# revB.net
KiCad netlist of a schematic drawn in EAGLE
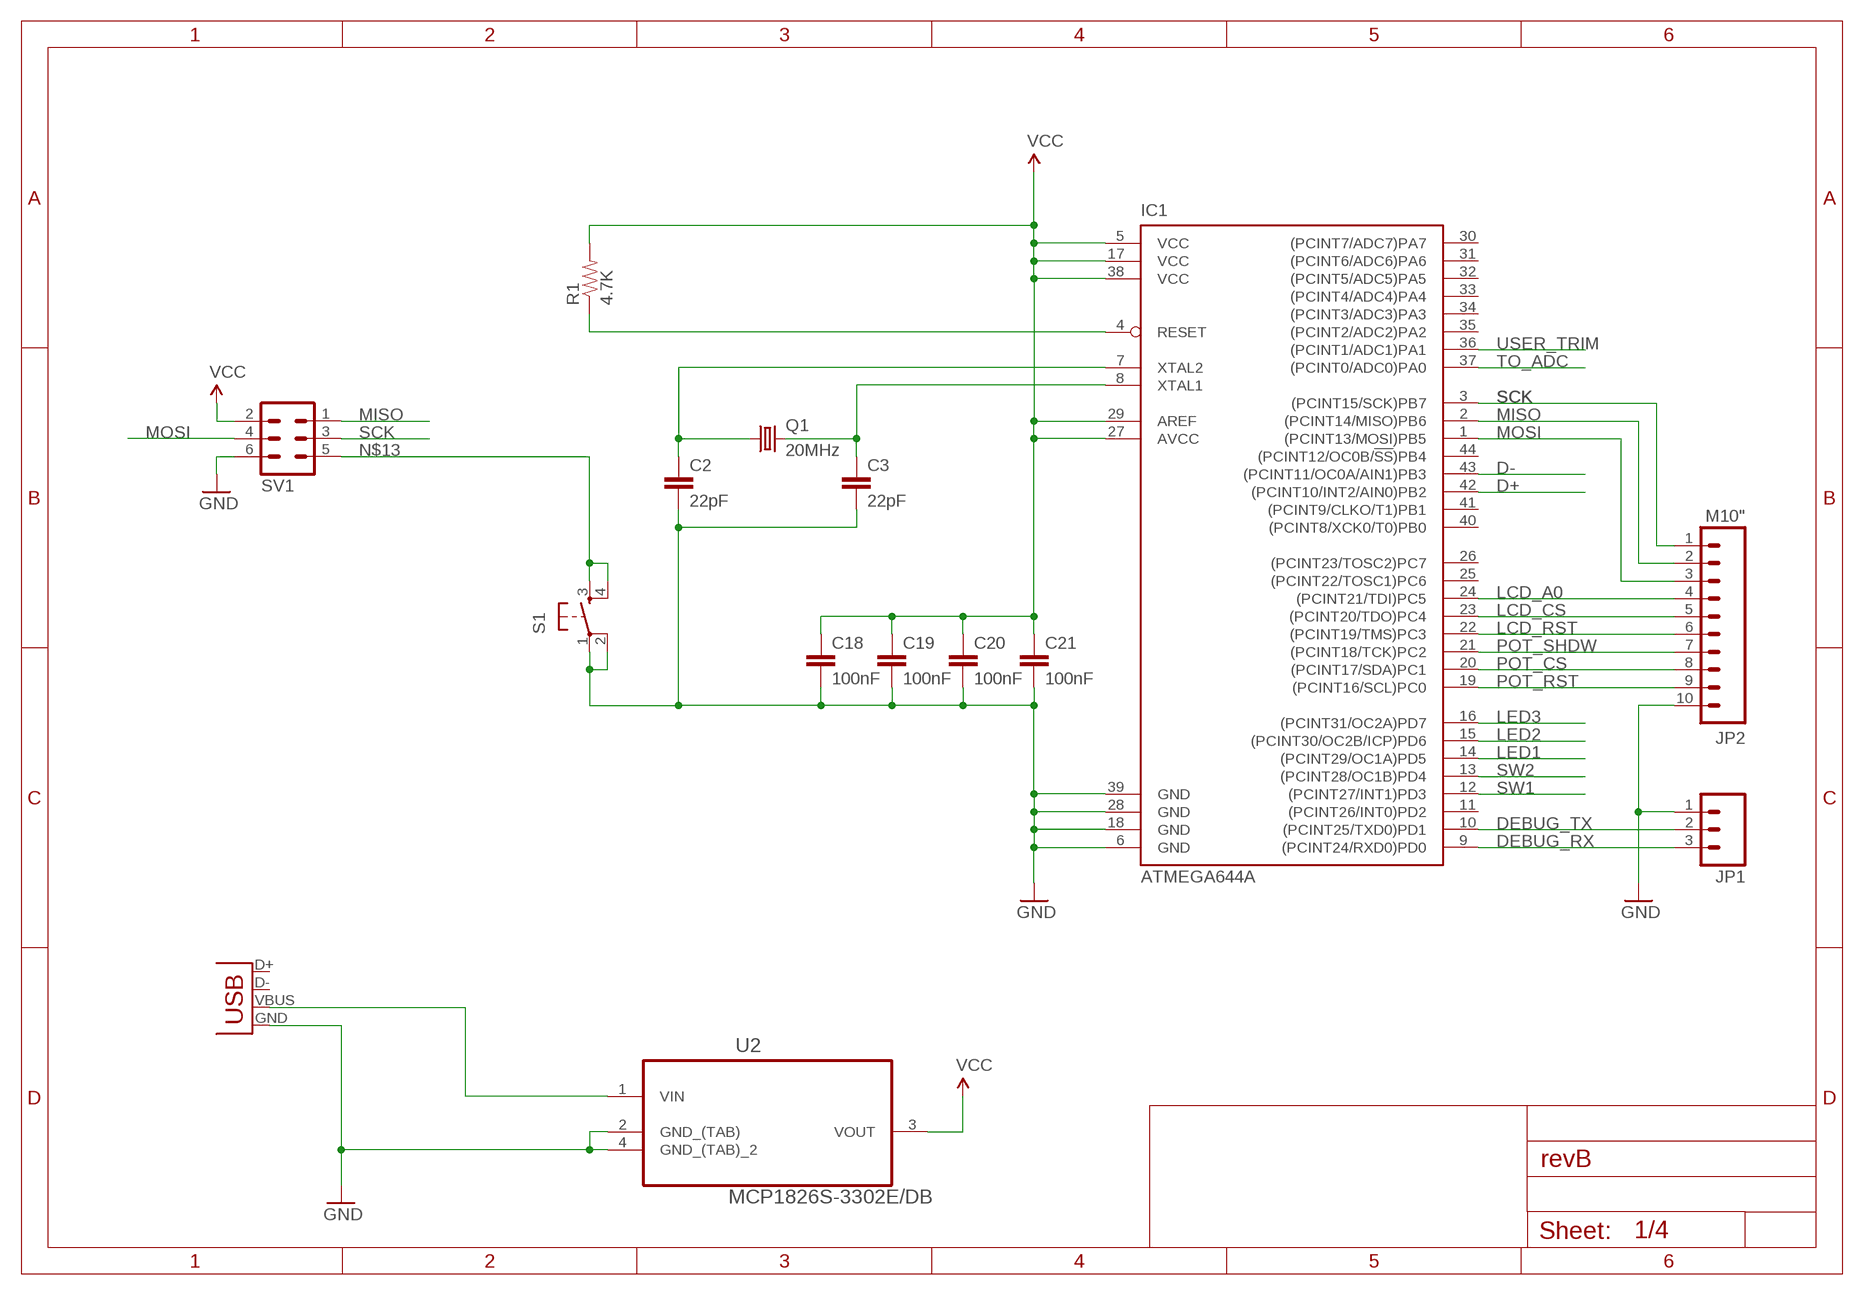
[diagram p0: schematic, sheet 1]
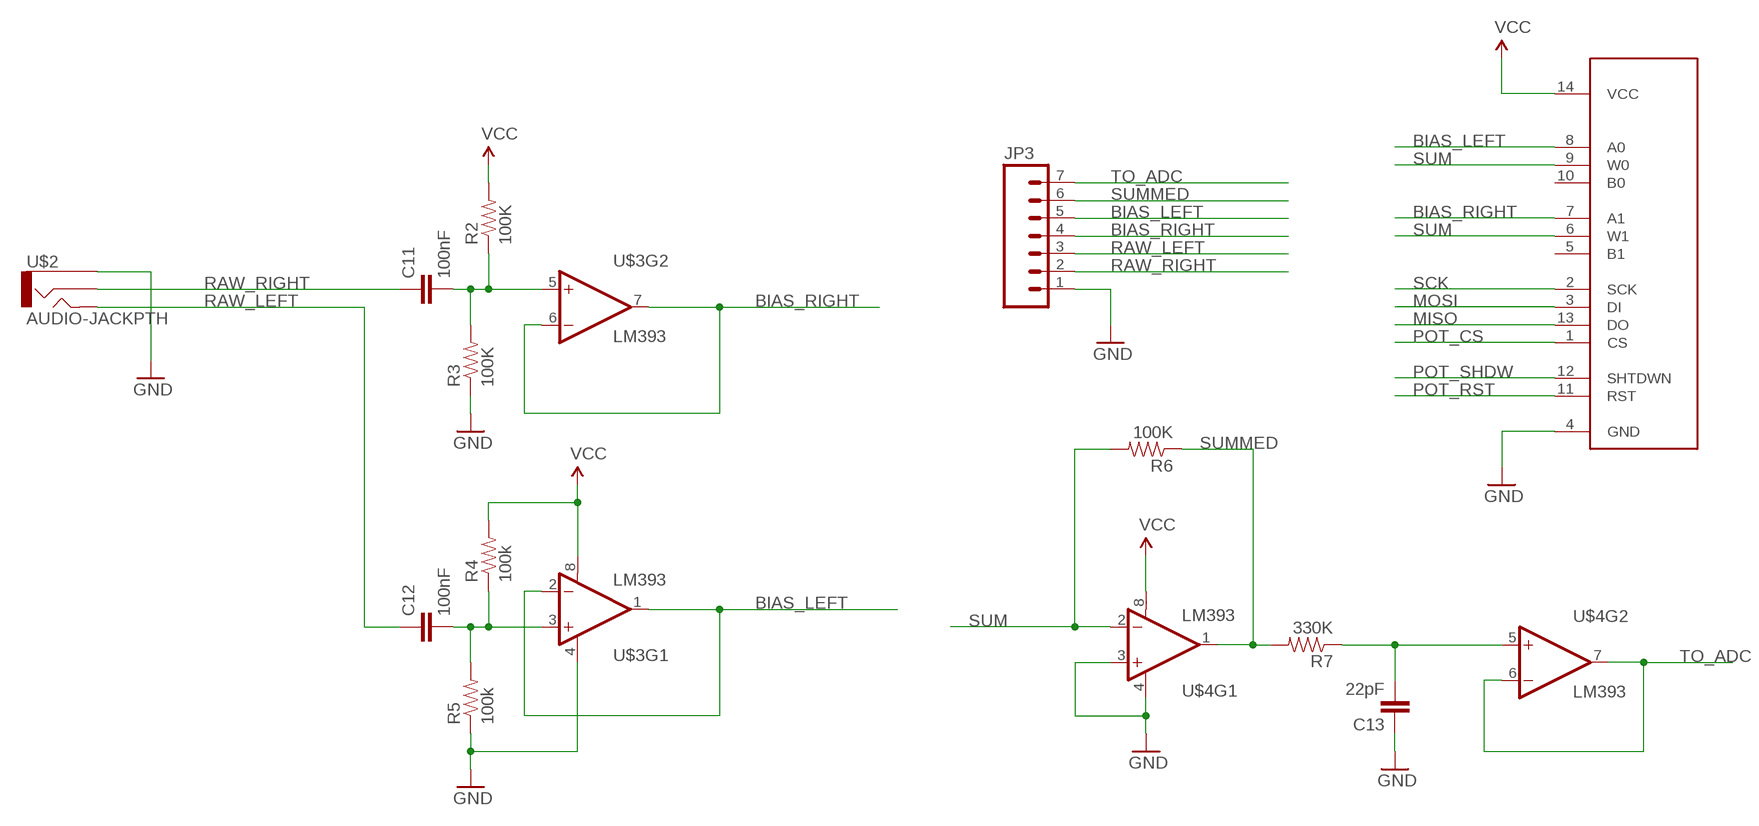
[diagram p1: schematic, sheet 2]
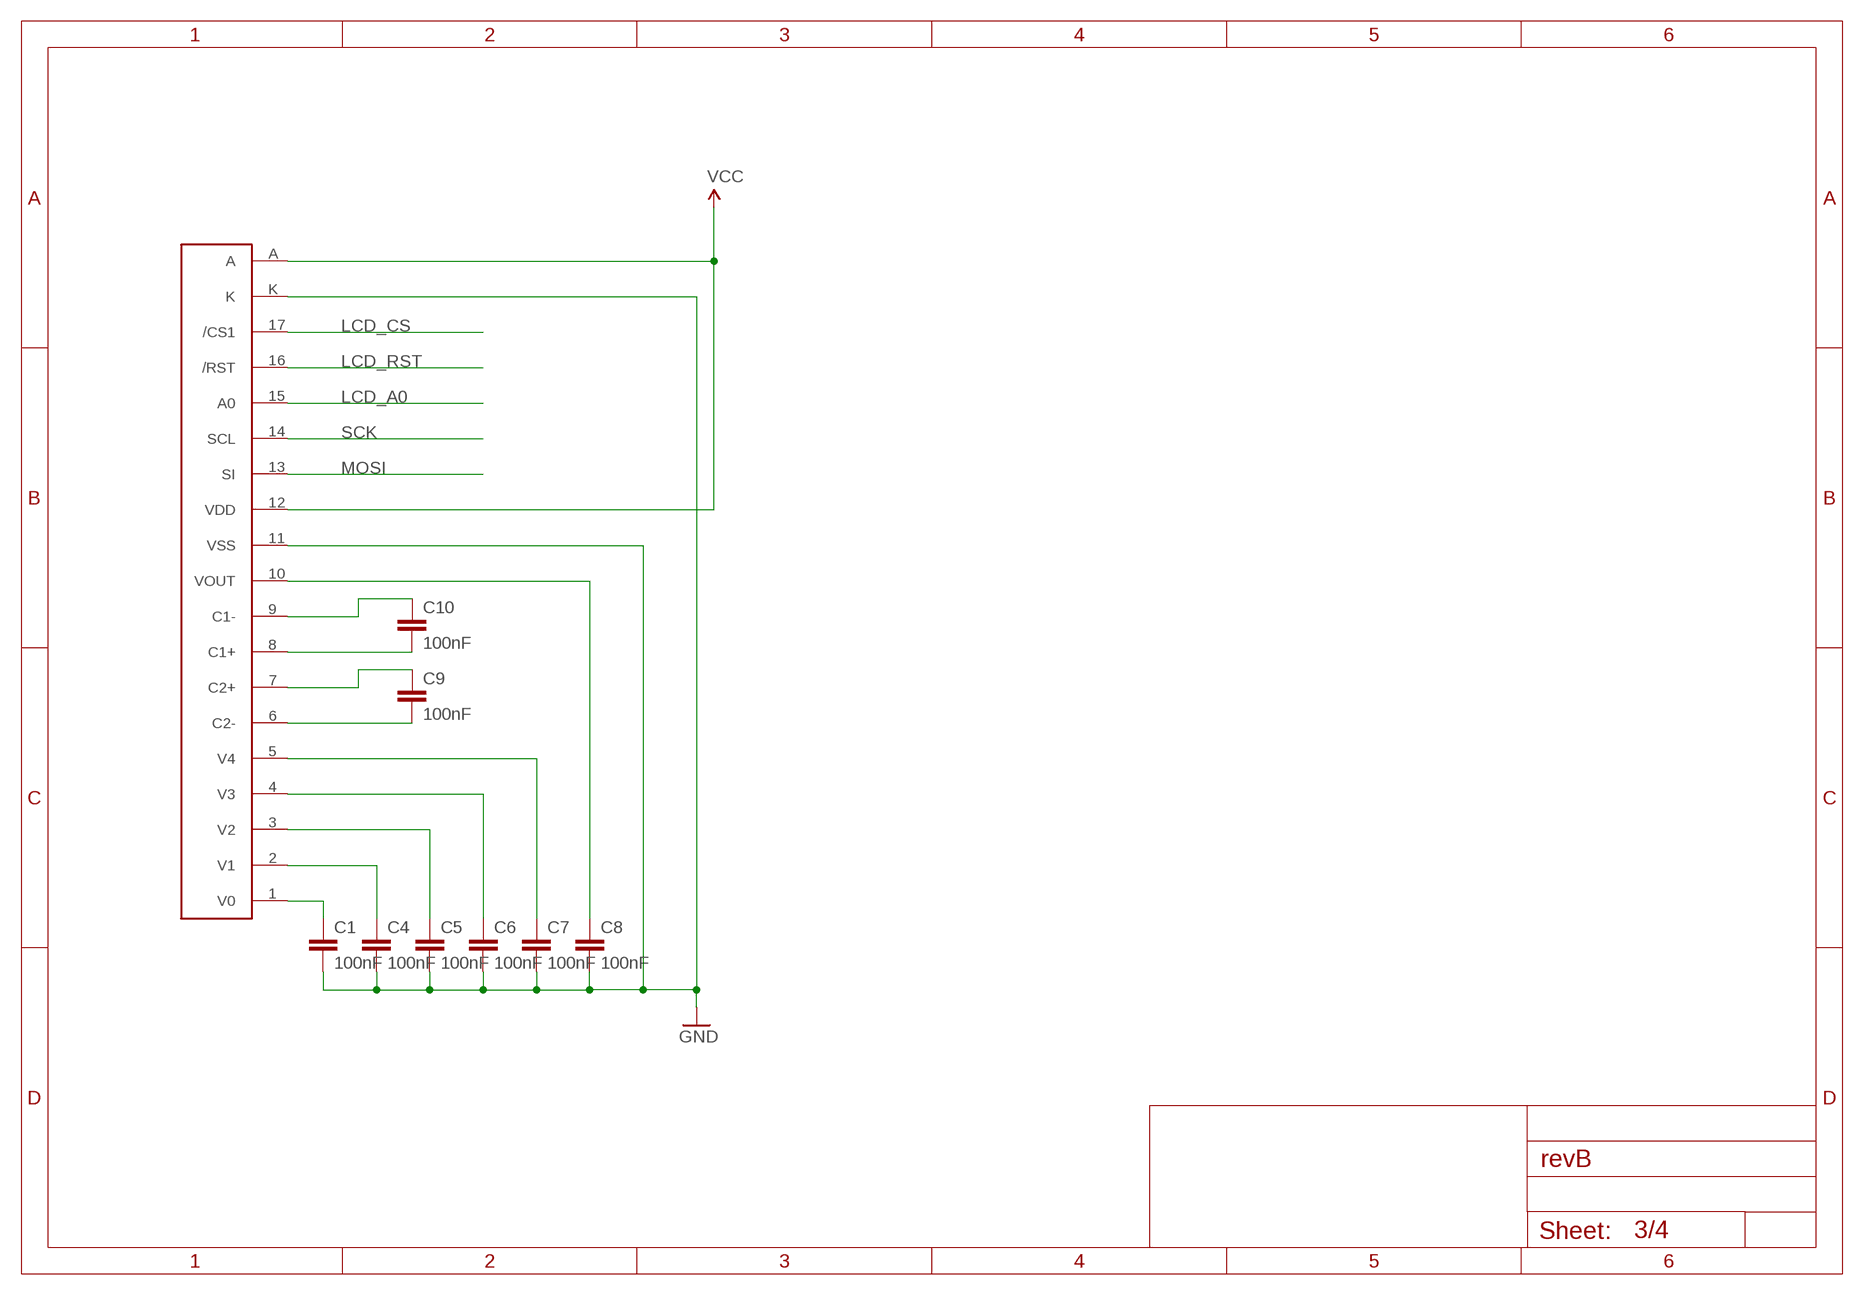
[diagram p2: schematic, sheet 3]
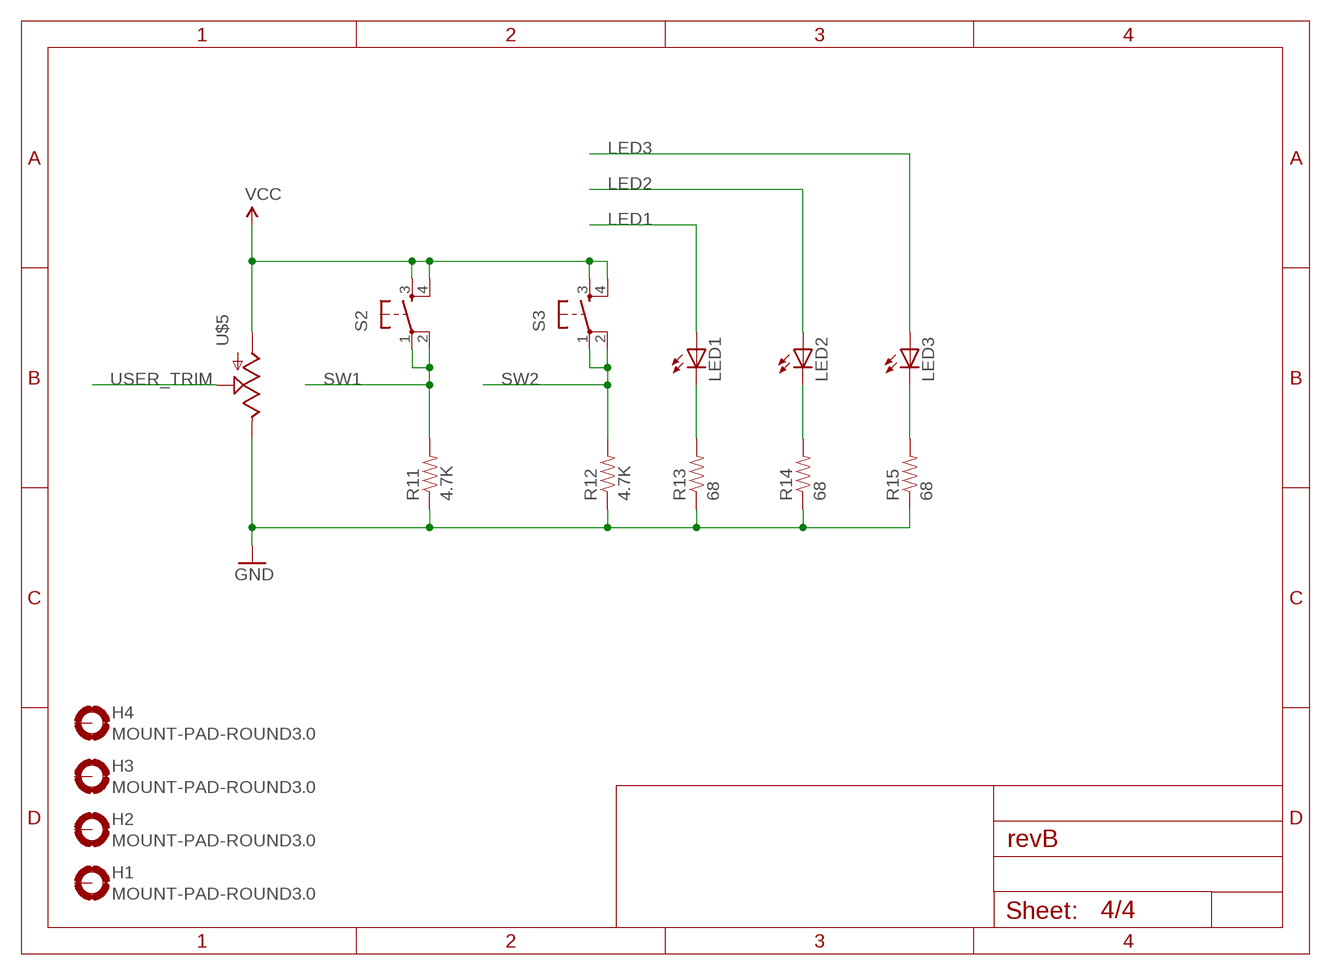
[diagram p3: schematic, sheet 4]

(export (version "E")
  (design (tool "Eeschema 10.0.6"))
  (components
    (comp (ref "C1")
      (value "100nF")
      (footprint "eagle-import:0805")
      (libsource (lib "eagle-import") (part "CAP0805"))
    )
    (comp (ref "C4")
      (value "100nF")
      (footprint "eagle-import:0805")
      (libsource (lib "eagle-import") (part "CAP0805"))
    )
    (comp (ref "C5")
      (value "100nF")
      (footprint "eagle-import:0805")
      (libsource (lib "eagle-import") (part "CAP0805"))
    )
    (comp (ref "C6")
      (value "100nF")
      (footprint "eagle-import:0805")
      (libsource (lib "eagle-import") (part "CAP0805"))
    )
    (comp (ref "C7")
      (value "100nF")
      (footprint "eagle-import:0805")
      (libsource (lib "eagle-import") (part "CAP0805"))
    )
    (comp (ref "C8")
      (value "100nF")
      (footprint "eagle-import:0805")
      (libsource (lib "eagle-import") (part "CAP0805"))
    )
    (comp (ref "C9")
      (value "100nF")
      (footprint "eagle-import:0805")
      (libsource (lib "eagle-import") (part "CAP0805"))
    )
    (comp (ref "C10")
      (value "100nF")
      (footprint "eagle-import:0805")
      (libsource (lib "eagle-import") (part "CAP0805"))
    )
    (comp (ref "U$1")
      (value "NHD_128X32")
      (footprint "eagle-import:NHD_128X32")
      (libsource (lib "eagle-import") (part "NHD_128X32"))
    )
    (comp (ref "C2")
      (value "22pF")
      (footprint "eagle-import:0805")
      (libsource (lib "eagle-import") (part "CAP0805"))
    )
    (comp (ref "C3")
      (value "22pF")
      (footprint "eagle-import:0805")
      (libsource (lib "eagle-import") (part "CAP0805"))
    )
    (comp (ref "C18")
      (value "100nF")
      (footprint "eagle-import:0805")
      (libsource (lib "eagle-import") (part "CAP0805"))
    )
    (comp (ref "C19")
      (value "100nF")
      (footprint "eagle-import:0805")
      (libsource (lib "eagle-import") (part "CAP0805"))
    )
    (comp (ref "C20")
      (value "100nF")
      (footprint "eagle-import:0805")
      (libsource (lib "eagle-import") (part "CAP0805"))
    )
    (comp (ref "C21")
      (value "100nF")
      (footprint "eagle-import:0805")
      (libsource (lib "eagle-import") (part "CAP0805"))
    )
    (comp (ref "IC1")
      (value "ATMEGA644A")
      (footprint "eagle-import:TQFP44")
      (fields (field (name "MPN") "ATMEGA644PV-10AU"))
      (libsource (lib "eagle-import") (part "ATMEGA644A"))
    )
    (comp (ref "JP1")
      (value "M03PTH")
      (footprint "eagle-import:1X03")
      (libsource (lib "eagle-import") (part "M03PTH"))
    )
    (comp (ref "JP2")
      (value "M10\"")
      (footprint "eagle-import:1X10")
      (libsource (lib "eagle-import") (part "M10{dblquote}"))
    )
    (comp (ref "Q1")
      (value "20MHz")
      (footprint "eagle-import:HC49U-V")
      (libsource (lib "eagle-import") (part "CRYSTALHC49UV"))
    )
    (comp (ref "R1")
      (value "4.7K")
      (footprint "eagle-import:1206")
      (libsource (lib "eagle-import") (part "RESISTOR1206"))
    )
    (comp (ref "S1")
      (value "TAC_SWITCHPTH")
      (footprint "eagle-import:TACTILE-PTH")
      (libsource (lib "eagle-import") (part "TAC_SWITCHPTH"))
    )
    (comp (ref "SV1")
      (value "MA03-2")
      (footprint "eagle-import:MA03-2")
      (libsource (lib "eagle-import") (part "MA03-2"))
    )
    (comp (ref "U2")
      (value "MCP1826S-3302E/DB")
      (footprint "eagle-import:SOT230P700X180-4N")
      (libsource (lib "eagle-import") (part "MCP1826S-3302E/DB"))
    )
    (comp (ref "X2")
      (value "USB-MB-H")
      (footprint "eagle-import:USB-MB-H")
      (libsource (lib "eagle-import") (part "USB-MB-H"))
    )
    (comp (ref "H1")
      (value "MOUNT-PAD-ROUND3.0")
      (footprint "eagle-import:3,0-PAD")
      (libsource (lib "eagle-import") (part "MOUNT-PAD-ROUND3.0"))
    )
    (comp (ref "H2")
      (value "MOUNT-PAD-ROUND3.0")
      (footprint "eagle-import:3,0-PAD")
      (libsource (lib "eagle-import") (part "MOUNT-PAD-ROUND3.0"))
    )
    (comp (ref "H3")
      (value "MOUNT-PAD-ROUND3.0")
      (footprint "eagle-import:3,0-PAD")
      (libsource (lib "eagle-import") (part "MOUNT-PAD-ROUND3.0"))
    )
    (comp (ref "H4")
      (value "MOUNT-PAD-ROUND3.0")
      (footprint "eagle-import:3,0-PAD")
      (libsource (lib "eagle-import") (part "MOUNT-PAD-ROUND3.0"))
    )
    (comp (ref "LED1")
      (value "LED1206")
      (footprint "eagle-import:LED-1206")
      (libsource (lib "eagle-import") (part "LED1206"))
    )
    (comp (ref "LED2")
      (value "LED1206")
      (footprint "eagle-import:LED-1206")
      (libsource (lib "eagle-import") (part "LED1206"))
    )
    (comp (ref "LED3")
      (value "LED1206")
      (footprint "eagle-import:LED-1206")
      (libsource (lib "eagle-import") (part "LED1206"))
    )
    (comp (ref "R11")
      (value "4.7K")
      (footprint "eagle-import:1206")
      (libsource (lib "eagle-import") (part "RESISTOR1206"))
    )
    (comp (ref "R12")
      (value "4.7K")
      (footprint "eagle-import:1206")
      (libsource (lib "eagle-import") (part "RESISTOR1206"))
    )
    (comp (ref "R13")
      (value "68")
      (footprint "eagle-import:1206")
      (libsource (lib "eagle-import") (part "RESISTOR1206"))
    )
    (comp (ref "R14")
      (value "68")
      (footprint "eagle-import:1206")
      (libsource (lib "eagle-import") (part "RESISTOR1206"))
    )
    (comp (ref "R15")
      (value "68")
      (footprint "eagle-import:1206")
      (libsource (lib "eagle-import") (part "RESISTOR1206"))
    )
    (comp (ref "S2")
      (value "TAC_SWITCHPTH")
      (footprint "eagle-import:TACTILE-PTH")
      (libsource (lib "eagle-import") (part "TAC_SWITCHPTH"))
    )
    (comp (ref "S3")
      (value "TAC_SWITCHPTH")
      (footprint "eagle-import:TACTILE-PTH")
      (libsource (lib "eagle-import") (part "TAC_SWITCHPTH"))
    )
    (comp (ref "U$5")
      (value "POTTRIM")
      (footprint "eagle-import:TRIM_POT")
      (libsource (lib "eagle-import") (part "POTTRIM"))
    )
    (comp (ref "C11")
      (value "100nF")
      (footprint "eagle-import:0805")
      (libsource (lib "eagle-import") (part "CAP0805"))
    )
    (comp (ref "C12")
      (value "100nF")
      (footprint "eagle-import:0805")
      (libsource (lib "eagle-import") (part "CAP0805"))
    )
    (comp (ref "C13")
      (value "22pF")
      (footprint "eagle-import:0805")
      (libsource (lib "eagle-import") (part "CAP0805"))
    )
    (comp (ref "JP3")
      (value "M07")
      (footprint "eagle-import:1X07")
      (libsource (lib "eagle-import") (part "M07"))
    )
    (comp (ref "R2")
      (value "100K")
      (footprint "eagle-import:1206")
      (libsource (lib "eagle-import") (part "RESISTOR1206"))
    )
    (comp (ref "R3")
      (value "100K")
      (footprint "eagle-import:1206")
      (libsource (lib "eagle-import") (part "RESISTOR1206"))
    )
    (comp (ref "R4")
      (value "100k")
      (footprint "eagle-import:1206")
      (libsource (lib "eagle-import") (part "RESISTOR1206"))
    )
    (comp (ref "R5")
      (value "100k")
      (footprint "eagle-import:1206")
      (libsource (lib "eagle-import") (part "RESISTOR1206"))
    )
    (comp (ref "R6")
      (value "100K")
      (footprint "eagle-import:1206")
      (libsource (lib "eagle-import") (part "RESISTOR1206"))
    )
    (comp (ref "R7")
      (value "330K")
      (footprint "eagle-import:1206")
      (libsource (lib "eagle-import") (part "RESISTOR1206"))
    )
    (comp (ref "U$2")
      (value "AUDIO-JACKPTH")
      (footprint "eagle-import:AUDIO-JACK")
      (libsource (lib "eagle-import") (part "AUDIO-JACKPTH"))
    )
    (comp (ref "U$3")
      (value "LM393")
      (footprint "eagle-import:SO08")
      (libsource (lib "eagle-import") (part "LM393"))
    )
    (comp (ref "U$4")
      (value "LM393")
      (footprint "eagle-import:SO08")
      (libsource (lib "eagle-import") (part "LM393"))
    )
    (comp (ref "U1")
      (value "MCP42XXX")
      (footprint "eagle-import:SO014")
      (libsource (lib "eagle-import") (part "MCP42XXX"))
    )
  )
  (nets
    (net (code "1") (name "BIAS_LEFT") (class "Default")
      (node (ref "JP3") (pin "5") (pinfunction "5_5") (pintype "passive"))
      (node (ref "U$3") (pin "1") (pinfunction "OUT_1") (pintype "output"))
      (node (ref "U$3") (pin "2") (pinfunction "-IN_2") (pintype "input"))
      (node (ref "U1") (pin "8") (pinfunction "A0_8") (pintype "bidirectional"))
    )
    (net (code "2") (name "BIAS_RIGHT") (class "Default")
      (node (ref "JP3") (pin "4") (pinfunction "4_4") (pintype "passive"))
      (node (ref "U$3") (pin "6") (pinfunction "-IN_6") (pintype "input"))
      (node (ref "U$3") (pin "7") (pinfunction "OUT_7") (pintype "output"))
      (node (ref "U1") (pin "7") (pinfunction "A1_7") (pintype "bidirectional"))
    )
    (net (code "3") (name "D+") (class "Default")
      (node (ref "IC1") (pin "42") (pinfunction "(PCINT10/INT2/AIN0)PB2_42") (pintype "bidirectional"))
    )
    (net (code "4") (name "D-") (class "Default")
      (node (ref "IC1") (pin "43") (pinfunction "(PCINT11/OC0A/AIN1)PB3_43") (pintype "bidirectional"))
    )
    (net (code "5") (name "DEBUG_RX") (class "Default")
      (node (ref "IC1") (pin "9") (pinfunction "(PCINT24/RXD0)PD0_9") (pintype "bidirectional"))
      (node (ref "JP1") (pin "3") (pinfunction "3_3") (pintype "passive"))
    )
    (net (code "6") (name "DEBUG_TX") (class "Default")
      (node (ref "IC1") (pin "10") (pinfunction "(PCINT25/TXD0)PD1_10") (pintype "bidirectional"))
      (node (ref "JP1") (pin "2") (pinfunction "2_2") (pintype "passive"))
    )
    (net (code "7") (name "GND") (class "Default")
      (node (ref "C1") (pin "2") (pinfunction "2_2") (pintype "passive"))
      (node (ref "C13") (pin "1") (pinfunction "1_1") (pintype "passive"))
      (node (ref "C18") (pin "2") (pinfunction "2_2") (pintype "passive"))
      (node (ref "C19") (pin "2") (pinfunction "2_2") (pintype "passive"))
      (node (ref "C2") (pin "2") (pinfunction "2_2") (pintype "passive"))
      (node (ref "C20") (pin "2") (pinfunction "2_2") (pintype "passive"))
      (node (ref "C21") (pin "2") (pinfunction "2_2") (pintype "passive"))
      (node (ref "C3") (pin "2") (pinfunction "2_2") (pintype "passive"))
      (node (ref "C4") (pin "2") (pinfunction "2_2") (pintype "passive"))
      (node (ref "C5") (pin "2") (pinfunction "2_2") (pintype "passive"))
      (node (ref "C6") (pin "2") (pinfunction "2_2") (pintype "passive"))
      (node (ref "C7") (pin "2") (pinfunction "2_2") (pintype "passive"))
      (node (ref "C8") (pin "2") (pinfunction "2_2") (pintype "passive"))
      (node (ref "IC1") (pin "18") (pinfunction "GND_18") (pintype "power_in"))
      (node (ref "IC1") (pin "28") (pinfunction "GND_28") (pintype "power_in"))
      (node (ref "IC1") (pin "39") (pinfunction "GND_39") (pintype "power_in"))
      (node (ref "IC1") (pin "6") (pinfunction "GND_6") (pintype "power_in"))
      (node (ref "JP1") (pin "1") (pinfunction "1_1") (pintype "passive"))
      (node (ref "JP2") (pin "10") (pinfunction "10_10") (pintype "passive"))
      (node (ref "JP3") (pin "1") (pinfunction "1_1") (pintype "passive"))
      (node (ref "R11") (pin "1") (pinfunction "1_1") (pintype "passive"))
      (node (ref "R12") (pin "1") (pinfunction "1_1") (pintype "passive"))
      (node (ref "R13") (pin "1") (pinfunction "1_1") (pintype "passive"))
      (node (ref "R14") (pin "1") (pinfunction "1_1") (pintype "passive"))
      (node (ref "R15") (pin "1") (pinfunction "1_1") (pintype "passive"))
      (node (ref "R3") (pin "1") (pinfunction "1_1") (pintype "passive"))
      (node (ref "R5") (pin "1") (pinfunction "1_1") (pintype "passive"))
      (node (ref "S1") (pin "1") (pinfunction "1_1") (pintype "passive"))
      (node (ref "S1") (pin "2") (pinfunction "2_2") (pintype "passive"))
      (node (ref "SV1") (pin "6") (pinfunction "6_6") (pintype "passive"))
      (node (ref "U$1") (pin "11") (pinfunction "VSS_11") (pintype "bidirectional"))
      (node (ref "U$1") (pin "K") (pinfunction "K_K") (pintype "bidirectional"))
      (node (ref "U$2") (pin "1") (pinfunction "1_1") (pintype "bidirectional"))
      (node (ref "U$3") (pin "4") (pinfunction "V-_4") (pintype "power_in"))
      (node (ref "U$4") (pin "3") (pinfunction "+IN_3") (pintype "input"))
      (node (ref "U$4") (pin "4") (pinfunction "V-_4") (pintype "power_in"))
      (node (ref "U$5") (pin "2") (pinfunction "E_2") (pintype "passive"))
      (node (ref "U1") (pin "4") (pinfunction "GND_4") (pintype "bidirectional"))
      (node (ref "U2") (pin "2") (pinfunction "GND_(TAB)_2") (pintype "passive"))
      (node (ref "U2") (pin "4") (pinfunction "GND_(TAB)_2_4") (pintype "passive"))
      (node (ref "X2") (pin "GND") (pinfunction "GND_GND") (pintype "bidirectional"))
    )
    (net (code "8") (name "LCD_A0") (class "Default")
      (node (ref "IC1") (pin "24") (pinfunction "(PCINT21/TDI)PC5_24") (pintype "output"))
      (node (ref "JP2") (pin "4") (pinfunction "4_4") (pintype "passive"))
      (node (ref "U$1") (pin "15") (pinfunction "A0_15") (pintype "bidirectional"))
    )
    (net (code "9") (name "LCD_CS") (class "Default")
      (node (ref "IC1") (pin "23") (pinfunction "(PCINT20/TDO)PC4_23") (pintype "output"))
      (node (ref "JP2") (pin "5") (pinfunction "5_5") (pintype "passive"))
      (node (ref "U$1") (pin "17") (pinfunction "/CS1_17") (pintype "bidirectional"))
    )
    (net (code "10") (name "LCD_RST") (class "Default")
      (node (ref "IC1") (pin "22") (pinfunction "(PCINT19/TMS)PC3_22") (pintype "output"))
      (node (ref "JP2") (pin "6") (pinfunction "6_6") (pintype "passive"))
      (node (ref "U$1") (pin "16") (pinfunction "/RST_16") (pintype "bidirectional"))
    )
    (net (code "11") (name "LED1") (class "Default")
      (node (ref "IC1") (pin "14") (pinfunction "(PCINT29/OC1A)PD5_14") (pintype "bidirectional"))
      (node (ref "LED1") (pin "A") (pinfunction "A_A") (pintype "passive"))
    )
    (net (code "12") (name "LED2") (class "Default")
      (node (ref "IC1") (pin "15") (pinfunction "(PCINT30/OC2B/ICP)PD6_15") (pintype "bidirectional"))
      (node (ref "LED2") (pin "A") (pinfunction "A_A") (pintype "passive"))
    )
    (net (code "13") (name "LED3") (class "Default")
      (node (ref "IC1") (pin "16") (pinfunction "(PCINT31/OC2A)PD7_16") (pintype "bidirectional"))
      (node (ref "LED3") (pin "A") (pinfunction "A_A") (pintype "passive"))
    )
    (net (code "14") (name "MISO") (class "Default")
      (node (ref "IC1") (pin "2") (pinfunction "(PCINT14/MISO)PB6_2") (pintype "bidirectional"))
      (node (ref "JP2") (pin "2") (pinfunction "2_2") (pintype "passive"))
      (node (ref "SV1") (pin "1") (pinfunction "1_1") (pintype "passive"))
      (node (ref "U1") (pin "13") (pinfunction "DO_13") (pintype "bidirectional"))
    )
    (net (code "15") (name "MOSI") (class "Default")
      (node (ref "IC1") (pin "1") (pinfunction "(PCINT13/MOSI)PB5_1") (pintype "bidirectional"))
      (node (ref "JP2") (pin "3") (pinfunction "3_3") (pintype "passive"))
      (node (ref "SV1") (pin "4") (pinfunction "4_4") (pintype "passive"))
      (node (ref "U$1") (pin "13") (pinfunction "SI_13") (pintype "bidirectional"))
      (node (ref "U1") (pin "3") (pinfunction "DI_3") (pintype "bidirectional"))
    )
    (net (code "16") (name "N$13") (class "Default")
      (node (ref "S1") (pin "3") (pinfunction "3_3") (pintype "passive"))
      (node (ref "S1") (pin "4") (pinfunction "4_4") (pintype "passive"))
      (node (ref "SV1") (pin "5") (pinfunction "5_5") (pintype "passive"))
    )
    (net (code "17") (name "Net-(IC1-RESET)") (class "Default")
      (node (ref "IC1") (pin "4") (pinfunction "RESET_4") (pintype "input"))
      (node (ref "R1") (pin "1") (pinfunction "1_1") (pintype "passive"))
    )
    (net (code "18") (name "Net-(IC1-XTAL1)") (class "Default")
      (node (ref "C3") (pin "1") (pinfunction "1_1") (pintype "passive"))
      (node (ref "IC1") (pin "8") (pinfunction "XTAL1_8") (pintype "bidirectional"))
      (node (ref "Q1") (pin "2") (pinfunction "2_2") (pintype "passive"))
    )
    (net (code "19") (name "Net-(IC1-XTAL2)") (class "Default")
      (node (ref "C2") (pin "1") (pinfunction "1_1") (pintype "passive"))
      (node (ref "IC1") (pin "7") (pinfunction "XTAL2_7") (pintype "bidirectional"))
      (node (ref "Q1") (pin "1") (pinfunction "1_1") (pintype "passive"))
    )
    (net (code "20") (name "Net-(LED1-PadC)") (class "Default")
      (node (ref "LED1") (pin "C") (pinfunction "C_C") (pintype "passive"))
      (node (ref "R13") (pin "2") (pinfunction "2_2") (pintype "passive"))
    )
    (net (code "21") (name "Net-(LED2-PadC)") (class "Default")
      (node (ref "LED2") (pin "C") (pinfunction "C_C") (pintype "passive"))
      (node (ref "R14") (pin "2") (pinfunction "2_2") (pintype "passive"))
    )
    (net (code "22") (name "Net-(LED3-PadC)") (class "Default")
      (node (ref "LED3") (pin "C") (pinfunction "C_C") (pintype "passive"))
      (node (ref "R15") (pin "2") (pinfunction "2_2") (pintype "passive"))
    )
    (net (code "23") (name "Net-(U$1-C1+)") (class "Default")
      (node (ref "C10") (pin "2") (pinfunction "2_2") (pintype "passive"))
      (node (ref "U$1") (pin "8") (pinfunction "C1+_8") (pintype "bidirectional"))
    )
    (net (code "24") (name "Net-(U$1-C1-)") (class "Default")
      (node (ref "C10") (pin "1") (pinfunction "1_1") (pintype "passive"))
      (node (ref "U$1") (pin "9") (pinfunction "C1-_9") (pintype "bidirectional"))
    )
    (net (code "25") (name "Net-(U$1-C2+)") (class "Default")
      (node (ref "C9") (pin "1") (pinfunction "1_1") (pintype "passive"))
      (node (ref "U$1") (pin "7") (pinfunction "C2+_7") (pintype "bidirectional"))
    )
    (net (code "26") (name "Net-(U$1-C2-)") (class "Default")
      (node (ref "C9") (pin "2") (pinfunction "2_2") (pintype "passive"))
      (node (ref "U$1") (pin "6") (pinfunction "C2-_6") (pintype "bidirectional"))
    )
    (net (code "27") (name "Net-(U$1-V0)") (class "Default")
      (node (ref "C1") (pin "1") (pinfunction "1_1") (pintype "passive"))
      (node (ref "U$1") (pin "1") (pinfunction "V0_1") (pintype "bidirectional"))
    )
    (net (code "28") (name "Net-(U$1-V1)") (class "Default")
      (node (ref "C4") (pin "1") (pinfunction "1_1") (pintype "passive"))
      (node (ref "U$1") (pin "2") (pinfunction "V1_2") (pintype "bidirectional"))
    )
    (net (code "29") (name "Net-(U$1-V2)") (class "Default")
      (node (ref "C5") (pin "1") (pinfunction "1_1") (pintype "passive"))
      (node (ref "U$1") (pin "3") (pinfunction "V2_3") (pintype "bidirectional"))
    )
    (net (code "30") (name "Net-(U$1-V3)") (class "Default")
      (node (ref "C6") (pin "1") (pinfunction "1_1") (pintype "passive"))
      (node (ref "U$1") (pin "4") (pinfunction "V3_4") (pintype "bidirectional"))
    )
    (net (code "31") (name "Net-(U$1-V4)") (class "Default")
      (node (ref "C7") (pin "1") (pinfunction "1_1") (pintype "passive"))
      (node (ref "U$1") (pin "5") (pinfunction "V4_5") (pintype "bidirectional"))
    )
    (net (code "32") (name "Net-(U$1-VOUT)") (class "Default")
      (node (ref "C8") (pin "1") (pinfunction "1_1") (pintype "passive"))
      (node (ref "U$1") (pin "10") (pinfunction "VOUT_10") (pintype "bidirectional"))
    )
    (net (code "33") (name "Net-(U$3A-+IN)") (class "Default")
      (node (ref "C12") (pin "2") (pinfunction "2_2") (pintype "passive"))
      (node (ref "R4") (pin "1") (pinfunction "1_1") (pintype "passive"))
      (node (ref "R5") (pin "2") (pinfunction "2_2") (pintype "passive"))
      (node (ref "U$3") (pin "3") (pinfunction "+IN_3") (pintype "input"))
    )
    (net (code "34") (name "Net-(U$3B-+IN)") (class "Default")
      (node (ref "C11") (pin "2") (pinfunction "2_2") (pintype "passive"))
      (node (ref "R2") (pin "1") (pinfunction "1_1") (pintype "passive"))
      (node (ref "R3") (pin "2") (pinfunction "2_2") (pintype "passive"))
      (node (ref "U$3") (pin "5") (pinfunction "+IN_5") (pintype "input"))
    )
    (net (code "35") (name "Net-(U$4B-+IN)") (class "Default")
      (node (ref "C13") (pin "2") (pinfunction "2_2") (pintype "passive"))
      (node (ref "R7") (pin "1") (pinfunction "1_1") (pintype "passive"))
      (node (ref "U$4") (pin "5") (pinfunction "+IN_5") (pintype "input"))
    )
    (net (code "36") (name "Net-(U2-VIN)") (class "Default")
      (node (ref "U2") (pin "1") (pinfunction "VIN_1") (pintype "input"))
      (node (ref "X2") (pin "VBUS") (pinfunction "VBUS_VBUS") (pintype "bidirectional"))
    )
    (net (code "37") (name "POT_CS") (class "Default")
      (node (ref "IC1") (pin "20") (pinfunction "(PCINT17/SDA)PC1_20") (pintype "output"))
      (node (ref "JP2") (pin "8") (pinfunction "8_8") (pintype "passive"))
      (node (ref "U1") (pin "1") (pinfunction "CS_1") (pintype "bidirectional"))
    )
    (net (code "38") (name "POT_RST") (class "Default")
      (node (ref "IC1") (pin "19") (pinfunction "(PCINT16/SCL)PC0_19") (pintype "output"))
      (node (ref "JP2") (pin "9") (pinfunction "9_9") (pintype "passive"))
      (node (ref "U1") (pin "11") (pinfunction "RST_11") (pintype "bidirectional"))
    )
    (net (code "39") (name "POT_SHDW") (class "Default")
      (node (ref "IC1") (pin "21") (pinfunction "(PCINT18/TCK)PC2_21") (pintype "output"))
      (node (ref "JP2") (pin "7") (pinfunction "7_7") (pintype "passive"))
      (node (ref "U1") (pin "12") (pinfunction "SHTDWN_12") (pintype "bidirectional"))
    )
    (net (code "40") (name "RAW_LEFT") (class "Default")
      (node (ref "C12") (pin "1") (pinfunction "1_1") (pintype "passive"))
      (node (ref "JP3") (pin "3") (pinfunction "3_3") (pintype "passive"))
      (node (ref "U$2") (pin "5") (pinfunction "5_5") (pintype "bidirectional"))
    )
    (net (code "41") (name "RAW_RIGHT") (class "Default")
      (node (ref "C11") (pin "1") (pinfunction "1_1") (pintype "passive"))
      (node (ref "JP3") (pin "2") (pinfunction "2_2") (pintype "passive"))
      (node (ref "U$2") (pin "2") (pinfunction "2_2") (pintype "bidirectional"))
    )
    (net (code "42") (name "SCK") (class "Default")
      (node (ref "IC1") (pin "3") (pinfunction "(PCINT15/SCK)PB7_3") (pintype "bidirectional"))
      (node (ref "JP2") (pin "1") (pinfunction "1_1") (pintype "passive"))
      (node (ref "SV1") (pin "3") (pinfunction "3_3") (pintype "passive"))
      (node (ref "U$1") (pin "14") (pinfunction "SCL_14") (pintype "bidirectional"))
      (node (ref "U1") (pin "2") (pinfunction "SCK_2") (pintype "bidirectional"))
    )
    (net (code "43") (name "SUM") (class "Default")
      (node (ref "R6") (pin "2") (pinfunction "2_2") (pintype "passive"))
      (node (ref "U$4") (pin "2") (pinfunction "-IN_2") (pintype "input"))
      (node (ref "U1") (pin "6") (pinfunction "W1_6") (pintype "bidirectional"))
      (node (ref "U1") (pin "9") (pinfunction "W0_9") (pintype "bidirectional"))
    )
    (net (code "44") (name "SUMMED") (class "Default")
      (node (ref "JP3") (pin "6") (pinfunction "6_6") (pintype "passive"))
      (node (ref "R6") (pin "1") (pinfunction "1_1") (pintype "passive"))
      (node (ref "R7") (pin "2") (pinfunction "2_2") (pintype "passive"))
      (node (ref "U$4") (pin "1") (pinfunction "OUT_1") (pintype "output"))
    )
    (net (code "45") (name "SW1") (class "Default")
      (node (ref "IC1") (pin "12") (pinfunction "(PCINT27/INT1)PD3_12") (pintype "bidirectional"))
      (node (ref "R11") (pin "2") (pinfunction "2_2") (pintype "passive"))
      (node (ref "S2") (pin "1") (pinfunction "1_1") (pintype "passive"))
      (node (ref "S2") (pin "2") (pinfunction "2_2") (pintype "passive"))
    )
    (net (code "46") (name "SW2") (class "Default")
      (node (ref "IC1") (pin "13") (pinfunction "(PCINT28/OC1B)PD4_13") (pintype "bidirectional"))
      (node (ref "R12") (pin "2") (pinfunction "2_2") (pintype "passive"))
      (node (ref "S3") (pin "1") (pinfunction "1_1") (pintype "passive"))
      (node (ref "S3") (pin "2") (pinfunction "2_2") (pintype "passive"))
    )
    (net (code "47") (name "TO_ADC") (class "Default")
      (node (ref "IC1") (pin "37") (pinfunction "(PCINT0/ADC0)PA0_37") (pintype "bidirectional"))
      (node (ref "JP3") (pin "7") (pinfunction "7_7") (pintype "passive"))
      (node (ref "U$4") (pin "6") (pinfunction "-IN_6") (pintype "input"))
      (node (ref "U$4") (pin "7") (pinfunction "OUT_7") (pintype "output"))
    )
    (net (code "48") (name "USER_TRIM") (class "Default")
      (node (ref "IC1") (pin "36") (pinfunction "(PCINT1/ADC1)PA1_36") (pintype "bidirectional"))
      (node (ref "U$5") (pin "1") (pinfunction "S_1") (pintype "passive"))
    )
    (net (code "49") (name "VCC") (class "Default")
      (node (ref "C18") (pin "1") (pinfunction "1_1") (pintype "passive"))
      (node (ref "C19") (pin "1") (pinfunction "1_1") (pintype "passive"))
      (node (ref "C20") (pin "1") (pinfunction "1_1") (pintype "passive"))
      (node (ref "C21") (pin "1") (pinfunction "1_1") (pintype "passive"))
      (node (ref "IC1") (pin "17") (pinfunction "VCC_17") (pintype "power_in"))
      (node (ref "IC1") (pin "27") (pinfunction "AVCC_27") (pintype "power_in"))
      (node (ref "IC1") (pin "29") (pinfunction "AREF_29") (pintype "passive"))
      (node (ref "IC1") (pin "38") (pinfunction "VCC_38") (pintype "power_in"))
      (node (ref "IC1") (pin "5") (pinfunction "VCC_5") (pintype "power_in"))
      (node (ref "R1") (pin "2") (pinfunction "2_2") (pintype "passive"))
      (node (ref "R2") (pin "2") (pinfunction "2_2") (pintype "passive"))
      (node (ref "R4") (pin "2") (pinfunction "2_2") (pintype "passive"))
      (node (ref "S2") (pin "3") (pinfunction "3_3") (pintype "passive"))
      (node (ref "S2") (pin "4") (pinfunction "4_4") (pintype "passive"))
      (node (ref "S3") (pin "3") (pinfunction "3_3") (pintype "passive"))
      (node (ref "S3") (pin "4") (pinfunction "4_4") (pintype "passive"))
      (node (ref "SV1") (pin "2") (pinfunction "2_2") (pintype "passive"))
      (node (ref "U$1") (pin "12") (pinfunction "VDD_12") (pintype "bidirectional"))
      (node (ref "U$1") (pin "A") (pinfunction "A_A") (pintype "bidirectional"))
      (node (ref "U$3") (pin "8") (pinfunction "V+_8") (pintype "power_in"))
      (node (ref "U$4") (pin "8") (pinfunction "V+_8") (pintype "power_in"))
      (node (ref "U$5") (pin "3") (pinfunction "A_3") (pintype "passive"))
      (node (ref "U1") (pin "14") (pinfunction "VCC_14") (pintype "bidirectional"))
      (node (ref "U2") (pin "3") (pinfunction "VOUT_3") (pintype "output"))
    )
    (net (code "50") (name "unconnected-(H1-MOUNT-PadB3,0)") (class "Default")
      (node (ref "H1") (pin "B3,0") (pinfunction "MOUNT_B3,0") (pintype "passive"))
    )
    (net (code "51") (name "unconnected-(H2-MOUNT-PadB3,0)") (class "Default")
      (node (ref "H2") (pin "B3,0") (pinfunction "MOUNT_B3,0") (pintype "passive"))
    )
    (net (code "52") (name "unconnected-(H3-MOUNT-PadB3,0)") (class "Default")
      (node (ref "H3") (pin "B3,0") (pinfunction "MOUNT_B3,0") (pintype "passive"))
    )
    (net (code "53") (name "unconnected-(H4-MOUNT-PadB3,0)") (class "Default")
      (node (ref "H4") (pin "B3,0") (pinfunction "MOUNT_B3,0") (pintype "passive"))
    )
    (net (code "54") (name "unconnected-(IC1-(PCINT2{slash}ADC2)PA2-Pad35)") (class "Default")
      (node (ref "IC1") (pin "35") (pinfunction "(PCINT2/ADC2)PA2_35") (pintype "bidirectional"))
    )
    (net (code "55") (name "unconnected-(IC1-(PCINT3{slash}ADC3)PA3-Pad34)") (class "Default")
      (node (ref "IC1") (pin "34") (pinfunction "(PCINT3/ADC3)PA3_34") (pintype "bidirectional"))
    )
    (net (code "56") (name "unconnected-(IC1-(PCINT4{slash}ADC4)PA4-Pad33)") (class "Default")
      (node (ref "IC1") (pin "33") (pinfunction "(PCINT4/ADC4)PA4_33") (pintype "bidirectional"))
    )
    (net (code "57") (name "unconnected-(IC1-(PCINT5{slash}ADC5)PA5-Pad32)") (class "Default")
      (node (ref "IC1") (pin "32") (pinfunction "(PCINT5/ADC5)PA5_32") (pintype "bidirectional"))
    )
    (net (code "58") (name "unconnected-(IC1-(PCINT6{slash}ADC6)PA6-Pad31)") (class "Default")
      (node (ref "IC1") (pin "31") (pinfunction "(PCINT6/ADC6)PA6_31") (pintype "bidirectional"))
    )
    (net (code "59") (name "unconnected-(IC1-(PCINT7{slash}ADC7)PA7-Pad30)") (class "Default")
      (node (ref "IC1") (pin "30") (pinfunction "(PCINT7/ADC7)PA7_30") (pintype "bidirectional"))
    )
    (net (code "60") (name "unconnected-(IC1-(PCINT8{slash}XCK0{slash}T0)PB0-Pad40)") (class "Default")
      (node (ref "IC1") (pin "40") (pinfunction "(PCINT8/XCK0/T0)PB0_40") (pintype "bidirectional"))
    )
    (net (code "61") (name "unconnected-(IC1-(PCINT9{slash}CLKO{slash}T1)PB1-Pad41)") (class "Default")
      (node (ref "IC1") (pin "41") (pinfunction "(PCINT9/CLKO/T1)PB1_41") (pintype "bidirectional"))
    )
    (net (code "62") (name "unconnected-(IC1-(PCINT12{slash}OC0B{slash}~{SS})PB4-Pad44)") (class "Default")
      (node (ref "IC1") (pin "44") (pinfunction "(PCINT12/OC0B/~{SS})PB4_44") (pintype "bidirectional"))
    )
    (net (code "63") (name "unconnected-(IC1-(PCINT22{slash}TOSC1)PC6-Pad25)") (class "Default")
      (node (ref "IC1") (pin "25") (pinfunction "(PCINT22/TOSC1)PC6_25") (pintype "output"))
    )
    (net (code "64") (name "unconnected-(IC1-(PCINT23{slash}TOSC2)PC7-Pad26)") (class "Default")
      (node (ref "IC1") (pin "26") (pinfunction "(PCINT23/TOSC2)PC7_26") (pintype "output"))
    )
    (net (code "65") (name "unconnected-(IC1-(PCINT26{slash}INT0)PD2-Pad11)") (class "Default")
      (node (ref "IC1") (pin "11") (pinfunction "(PCINT26/INT0)PD2_11") (pintype "bidirectional"))
    )
    (net (code "66") (name "unconnected-(U1-B0-Pad10)") (class "Default")
      (node (ref "U1") (pin "10") (pinfunction "B0_10") (pintype "bidirectional"))
    )
    (net (code "67") (name "unconnected-(U1-B1-Pad5)") (class "Default")
      (node (ref "U1") (pin "5") (pinfunction "B1_5") (pintype "bidirectional"))
    )
    (net (code "68") (name "unconnected-(X2-PadD+)") (class "Default")
      (node (ref "X2") (pin "D+") (pinfunction "D+_D+") (pintype "bidirectional"))
    )
    (net (code "69") (name "unconnected-(X2-PadD-)") (class "Default")
      (node (ref "X2") (pin "D-") (pinfunction "D-_D-") (pintype "bidirectional"))
    )
  )
)
